# adafruit_flora_neopixel.net
KiCad netlist of a schematic drawn in Altium Designer
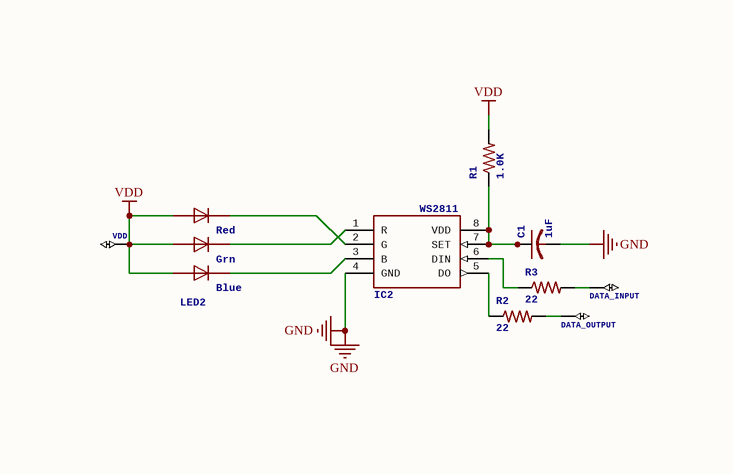
[diagram p0: adafruit flora neopixel.SchDoc]

(export (version "E")
  (design (tool "Eeschema 10.0.6"))
  (components
    (comp (ref "C1")
      (value "1uF")
      (footprint "C0805K")
      (description "CAPACITOR, American symbol")
      (libsource (lib "adafruit") (part "C-USC0805K"))
    )
    (comp (ref "DATA_INPUT")
      (value "SEWTAP0.5IN")
      (footprint "SEWINGTAP_0.5")
      (libsource (lib "adafruit") (part "SEWTAP0.5IN"))
    )
    (comp (ref "DATA_OUTPUT")
      (value "SEWTAP0.5IN")
      (footprint "SEWINGTAP_0.5")
      (libsource (lib "adafruit") (part "SEWTAP0.5IN"))
    )
    (comp (ref "IC2")
      (value "WS2811-SOP8")
      (footprint "SO08-SKINNYPADS")
      (fields (field (name "WS2811") "WS2811"))
      (libsource (lib "adafruit") (part "WS2811-SOP8"))
    )
    (comp (ref "LED2")
      (value "RGBLED5050")
      (footprint "RGBLED5050")
      (description "For 5050 RGB LEDs, the order of the LEDs may vary from one manufacturer to another!")
      (fields (field (name "RED") "Red") (field (name "GRN") "Grn") (field (name "BLUE") "Blue"))
      (libsource (lib "adafruit") (part "RGBLED5050"))
    )
    (comp (ref "R1")
      (value "1.0K")
      (footprint "R0805")
      (description "RESISTOR, American symbol")
      (libsource (lib "adafruit") (part "R-US_R0805"))
    )
    (comp (ref "R2")
      (value "22")
      (footprint "R0805")
      (description "RESISTOR, American symbol")
      (libsource (lib "adafruit") (part "R-US_R0805"))
    )
    (comp (ref "R3")
      (value "22")
      (footprint "R0805")
      (description "RESISTOR, American symbol")
      (libsource (lib "adafruit") (part "R-US_R0805"))
    )
    (comp (ref "VDD")
      (value "SEWTAP0.5IN")
      (footprint "SEWINGTAP_0.5")
      (libsource (lib "adafruit") (part "SEWTAP0.5IN"))
    )
  )
  (nets
    (net (code "1") (name "GND") (class "Default")
      (node (ref "C1") (pin "2") (pinfunction "2_2") (pintype "passive"))
      (node (ref "IC2") (pin "4") (pinfunction "GND_4") (pintype "power_in"))
    )
    (net (code "2") (name "Net-(DATA_INPUT-SEW)") (class "Default")
      (node (ref "DATA_INPUT") (pin "TAP") (pinfunction "SEW_TAP") (pintype "bidirectional"))
      (node (ref "R3") (pin "2") (pinfunction "2_2") (pintype "passive"))
    )
    (net (code "3") (name "Net-(DATA_OUTPUT-SEW)") (class "Default")
      (node (ref "DATA_OUTPUT") (pin "TAP") (pinfunction "SEW_TAP") (pintype "bidirectional"))
      (node (ref "R2") (pin "2") (pinfunction "2_2") (pintype "passive"))
    )
    (net (code "4") (name "Net-(IC2-B)") (class "Default")
      (node (ref "IC2") (pin "3") (pinfunction "B_3") (pintype "open_collector"))
      (node (ref "LED2") (pin "4") (pinfunction "BLUE_C_4") (pintype "bidirectional"))
    )
    (net (code "5") (name "Net-(IC2-DIN)") (class "Default")
      (node (ref "IC2") (pin "6") (pinfunction "DIN_6") (pintype "input"))
      (node (ref "R3") (pin "1") (pinfunction "1_1") (pintype "passive"))
    )
    (net (code "6") (name "Net-(IC2-DO)") (class "Default")
      (node (ref "IC2") (pin "5") (pinfunction "DO_5") (pintype "output"))
      (node (ref "R2") (pin "1") (pinfunction "1_1") (pintype "passive"))
    )
    (net (code "7") (name "Net-(IC2-G)") (class "Default")
      (node (ref "IC2") (pin "2") (pinfunction "G_2") (pintype "open_collector"))
      (node (ref "LED2") (pin "5") (pinfunction "RED_C_5") (pintype "bidirectional"))
    )
    (net (code "8") (name "Net-(IC2-R)") (class "Default")
      (node (ref "IC2") (pin "1") (pinfunction "R_1") (pintype "open_collector"))
      (node (ref "LED2") (pin "6") (pinfunction "GREEN_C_6") (pintype "bidirectional"))
    )
    (net (code "9") (name "Net-(IC2-SET)") (class "Default")
      (node (ref "C1") (pin "1") (pinfunction "1_1") (pintype "passive"))
      (node (ref "IC2") (pin "7") (pinfunction "SET_7") (pintype "input"))
      (node (ref "IC2") (pin "8") (pinfunction "VDD_8") (pintype "power_in"))
      (node (ref "R1") (pin "1") (pinfunction "1_1") (pintype "passive"))
    )
    (net (code "10") (name "VDD") (class "Default")
      (node (ref "LED2") (pin "1") (pinfunction "GREEN_A_1") (pintype "bidirectional"))
      (node (ref "LED2") (pin "2") (pinfunction "RED_A_2") (pintype "bidirectional"))
      (node (ref "LED2") (pin "3") (pinfunction "BLUE_A_3") (pintype "bidirectional"))
      (node (ref "R1") (pin "2") (pinfunction "2_2") (pintype "passive"))
      (node (ref "VDD") (pin "TAP") (pinfunction "SEW_TAP") (pintype "bidirectional"))
    )
  )
)
